# Auxilary.net
KiCad netlist of a schematic drawn in Altium Designer
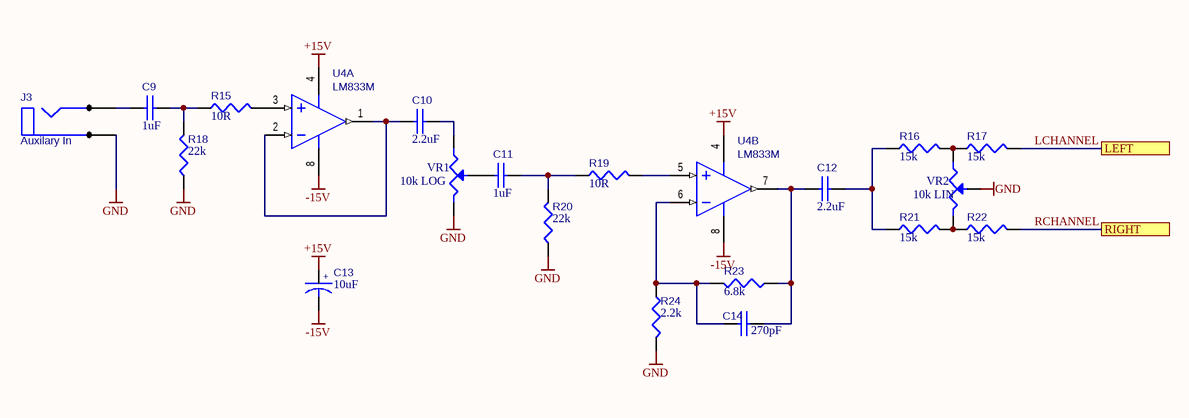
[diagram p0:  Auxilary.SchDoc]

(export (version "E")
  (design (tool "Eeschema 10.0.6"))
  (components
    (comp (ref "C9")
      (value "1uF")
      (footprint "RB.2/.4-NP")
      (description "Capacitor")
      (libsource (lib "*") (part "CAP"))
    )
    (comp (ref "C10")
      (value "2.2uF")
      (footprint "RB.2/.4-NP")
      (description "Capacitor")
      (libsource (lib "*") (part "CAP"))
    )
    (comp (ref "C11")
      (value "1uF")
      (footprint "RB.2/.4-NP")
      (description "Capacitor")
      (libsource (lib "*") (part "CAP"))
    )
    (comp (ref "C12")
      (value "2.2uF")
      (footprint "RB.2/.4-NP")
      (description "Capacitor")
      (libsource (lib "*") (part "CAP"))
    )
    (comp (ref "C13")
      (value "10uF")
      (footprint "RB.2/.4")
      (description "Bi-Polar Capacitor")
      (libsource (lib "*") (part "CAPACITOR POL"))
    )
    (comp (ref "C14")
      (value "270pF")
      (footprint "RAD0.2")
      (description "Capacitor")
      (libsource (lib "*") (part "CAP"))
    )
    (comp (ref "J3")
      (value "Auxilary In")
      (footprint "JACK-6.25MM")
      (libsource (lib "*") (part "PHONEJACK MONO"))
    )
    (comp (ref "R15")
      (value "10R")
      (footprint "AXIAL0.4")
      (description "Resistor")
      (libsource (lib "") (part "RES1_2"))
    )
    (comp (ref "R16")
      (value "15k")
      (footprint "AXIAL0.4")
      (description "Resistor")
      (libsource (lib "") (part "RES1_2"))
    )
    (comp (ref "R17")
      (value "15k")
      (footprint "AXIAL0.4")
      (description "Resistor")
      (libsource (lib "") (part "RES1_2"))
    )
    (comp (ref "R18")
      (value "22k")
      (footprint "AXIAL0.4")
      (description "Resistor")
      (libsource (lib "") (part "RES1_3"))
    )
    (comp (ref "R19")
      (value "10R")
      (footprint "AXIAL0.4")
      (description "Resistor")
      (libsource (lib "") (part "RES1_2"))
    )
    (comp (ref "R20")
      (value "22k")
      (footprint "AXIAL0.4")
      (description "Resistor")
      (libsource (lib "") (part "RES1_3"))
    )
    (comp (ref "R21")
      (value "15k")
      (footprint "AXIAL0.4")
      (description "Resistor")
      (libsource (lib "") (part "RES1_2"))
    )
    (comp (ref "R22")
      (value "15k")
      (footprint "AXIAL0.4")
      (description "Resistor")
      (libsource (lib "") (part "RES1_2"))
    )
    (comp (ref "R23")
      (value "6.8k")
      (footprint "AXIAL0.4")
      (description "Resistor")
      (libsource (lib "") (part "RES1_1"))
    )
    (comp (ref "R24")
      (value "2.2k")
      (footprint "AXIAL0.4")
      (description "Resistor")
      (libsource (lib "*") (part "RES1"))
    )
    (comp (ref "U4")
      (value "LM833M")
      (footprint "DIP8")
      (description "Fast Settling Dual Operational Amplifier")
      (libsource (lib "*") (part "LM833M"))
    )
    (comp (ref "VR1")
      (value "10k LOG")
      (footprint "POT - 24MM")
      (description "Potentiometer")
      (libsource (lib "*") (part "POT1"))
    )
    (comp (ref "VR2")
      (value "10k LIN")
      (footprint "POT - 24MM")
      (description "Potentiometer")
      (libsource (lib "*") (part "POT1"))
    )
  )
  (nets
    (net (code "1") (name "+15V") (class "Default")
      (node (ref "C13") (pin "1") (pinfunction "1_1") (pintype "passive"))
      (node (ref "U4") (pin "4") (pinfunction "V-_4") (pintype "power_in"))
    )
    (net (code "2") (name "-15V") (class "Default")
      (node (ref "C13") (pin "2") (pinfunction "2_2") (pintype "passive"))
      (node (ref "U4") (pin "8") (pinfunction "V+_8") (pintype "power_in"))
    )
    (net (code "3") (name "/LCHANNEL") (class "Default")
      (node (ref "R17") (pin "2") (pinfunction "2_2") (pintype "passive"))
    )
    (net (code "4") (name "/RCHANNEL") (class "Default")
      (node (ref "R22") (pin "2") (pinfunction "2_2") (pintype "passive"))
    )
    (net (code "5") (name "GND") (class "Default")
      (node (ref "J3") (pin "3") (pinfunction "C_3") (pintype "passive"))
      (node (ref "R18") (pin "1") (pinfunction "1_1") (pintype "passive"))
      (node (ref "R20") (pin "1") (pinfunction "1_1") (pintype "passive"))
      (node (ref "R24") (pin "2") (pinfunction "2_2") (pintype "passive"))
      (node (ref "VR1") (pin "3") (pinfunction "3_3") (pintype "passive"))
      (node (ref "VR2") (pin "2") (pinfunction "W_2") (pintype "passive"))
    )
    (net (code "6") (name "Net-(C9-Pad2)") (class "Default")
      (node (ref "C9") (pin "2") (pinfunction "2_2") (pintype "passive"))
      (node (ref "R15") (pin "1") (pinfunction "1_1") (pintype "passive"))
      (node (ref "R18") (pin "2") (pinfunction "2_2") (pintype "passive"))
    )
    (net (code "7") (name "Net-(C10-Pad2)") (class "Default")
      (node (ref "C10") (pin "2") (pinfunction "2_2") (pintype "passive"))
      (node (ref "VR1") (pin "1") (pinfunction "1_1") (pintype "passive"))
    )
    (net (code "8") (name "Net-(C11-Pad2)") (class "Default")
      (node (ref "C11") (pin "2") (pinfunction "2_2") (pintype "passive"))
      (node (ref "R19") (pin "1") (pinfunction "1_1") (pintype "passive"))
      (node (ref "R20") (pin "2") (pinfunction "2_2") (pintype "passive"))
    )
    (net (code "9") (name "Net-(C12-Pad2)") (class "Default")
      (node (ref "C12") (pin "2") (pinfunction "2_2") (pintype "passive"))
      (node (ref "R16") (pin "1") (pinfunction "1_1") (pintype "passive"))
      (node (ref "R21") (pin "1") (pinfunction "1_1") (pintype "passive"))
    )
    (net (code "10") (name "Net-(J3-A)") (class "Default")
      (node (ref "C9") (pin "1") (pinfunction "1_1") (pintype "passive"))
      (node (ref "J3") (pin "1") (pinfunction "A_1") (pintype "passive"))
    )
    (net (code "11") (name "Net-(R16-Pad2)") (class "Default")
      (node (ref "R16") (pin "2") (pinfunction "2_2") (pintype "passive"))
      (node (ref "R17") (pin "1") (pinfunction "1_1") (pintype "passive"))
      (node (ref "VR2") (pin "1") (pinfunction "1_1") (pintype "passive"))
    )
    (net (code "12") (name "Net-(R21-Pad2)") (class "Default")
      (node (ref "R21") (pin "2") (pinfunction "2_2") (pintype "passive"))
      (node (ref "R22") (pin "1") (pinfunction "1_1") (pintype "passive"))
      (node (ref "VR2") (pin "3") (pinfunction "3_3") (pintype "passive"))
    )
    (net (code "13") (name "Net-(U4A-IN1+)") (class "Default")
      (node (ref "R15") (pin "2") (pinfunction "2_2") (pintype "passive"))
      (node (ref "U4") (pin "3") (pinfunction "IN1+_3") (pintype "input"))
    )
    (net (code "14") (name "Net-(U4A-IN1-)") (class "Default")
      (node (ref "C10") (pin "1") (pinfunction "1_1") (pintype "passive"))
      (node (ref "U4") (pin "1") (pinfunction "OUT1_1") (pintype "output"))
      (node (ref "U4") (pin "2") (pinfunction "IN1-_2") (pintype "input"))
    )
    (net (code "15") (name "Net-(U4B-IN2+)") (class "Default")
      (node (ref "R19") (pin "2") (pinfunction "2_2") (pintype "passive"))
      (node (ref "U4") (pin "5") (pinfunction "IN2+_5") (pintype "input"))
    )
    (net (code "16") (name "Net-(U4B-IN2-)") (class "Default")
      (node (ref "C14") (pin "1") (pinfunction "1_1") (pintype "passive"))
      (node (ref "R23") (pin "2") (pinfunction "2_2") (pintype "passive"))
      (node (ref "R24") (pin "1") (pinfunction "1_1") (pintype "passive"))
      (node (ref "U4") (pin "6") (pinfunction "IN2-_6") (pintype "input"))
    )
    (net (code "17") (name "Net-(U4B-OUT2)") (class "Default")
      (node (ref "C12") (pin "1") (pinfunction "1_1") (pintype "passive"))
      (node (ref "C14") (pin "2") (pinfunction "2_2") (pintype "passive"))
      (node (ref "R23") (pin "1") (pinfunction "1_1") (pintype "passive"))
      (node (ref "U4") (pin "7") (pinfunction "OUT2_7") (pintype "output"))
    )
    (net (code "18") (name "Net-(VR1-W)") (class "Default")
      (node (ref "C11") (pin "1") (pinfunction "1_1") (pintype "passive"))
      (node (ref "VR1") (pin "2") (pinfunction "W_2") (pintype "passive"))
    )
  )
)
